# lght.net
KiCad netlist of a schematic drawn in Altium Designer
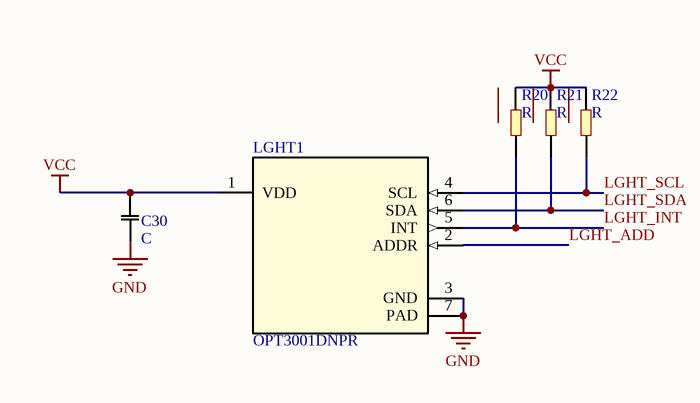
[diagram p0: lght.SchDoc]

(export (version "E")
  (design (tool "Eeschema 10.0.6"))
  (components
    (comp (ref "C30")
      (value "C")
      (footprint "402")
      (description "Capacitor")
      (libsource (lib "pass_comp") (part "C"))
    )
    (comp (ref "LGHT1")
      (value "OPT3001DNPR")
      (footprint "DNP0006A")
      (description "Imported")
      (fields (field (name "PARTNUMBER") "OPT3001DNP") (field (name "MANUFACTURER") "Texas Instruments"))
      (libsource (lib "env_sens") (part "OPT3001DNPR"))
    )
    (comp (ref "R20")
      (value "R")
      (footprint "402")
      (description "Resistor")
      (libsource (lib "pass_comp") (part "R"))
    )
    (comp (ref "R21")
      (value "R")
      (footprint "402")
      (description "Resistor")
      (libsource (lib "pass_comp") (part "R"))
    )
    (comp (ref "R22")
      (value "R")
      (footprint "402")
      (description "Resistor")
      (libsource (lib "pass_comp") (part "R"))
    )
  )
  (nets
    (net (code "1") (name "/LGHT_ADD") (class "Default")
      (node (ref "LGHT1") (pin "2") (pinfunction "ADDR_2") (pintype "input"))
    )
    (net (code "2") (name "/LGHT_INT") (class "Default")
      (node (ref "LGHT1") (pin "5") (pinfunction "INT_5") (pintype "output"))
      (node (ref "R20") (pin "1") (pintype "passive"))
    )
    (net (code "3") (name "/LGHT_SCL") (class "Default")
      (node (ref "LGHT1") (pin "4") (pinfunction "SCL_4") (pintype "input"))
      (node (ref "R22") (pin "1") (pintype "passive"))
    )
    (net (code "4") (name "/LGHT_SDA") (class "Default")
      (node (ref "LGHT1") (pin "6") (pinfunction "SDA_6") (pintype "input"))
      (node (ref "R21") (pin "1") (pintype "passive"))
    )
    (net (code "5") (name "GND") (class "Default")
      (node (ref "C30") (pin "1") (pintype "passive"))
      (node (ref "LGHT1") (pin "3") (pinfunction "GND_3") (pintype "power_in"))
      (node (ref "LGHT1") (pin "7") (pinfunction "PAD_7") (pintype "passive"))
    )
    (net (code "6") (name "VCC") (class "Default")
      (node (ref "C30") (pin "2") (pintype "passive"))
      (node (ref "LGHT1") (pin "1") (pinfunction "VDD_1") (pintype "power_in"))
      (node (ref "R20") (pin "2") (pintype "passive"))
      (node (ref "R21") (pin "2") (pintype "passive"))
      (node (ref "R22") (pin "2") (pintype "passive"))
    )
  )
)
